# 4_Power_ON_OFF.net
KiCad netlist of a schematic drawn in Altium Designer
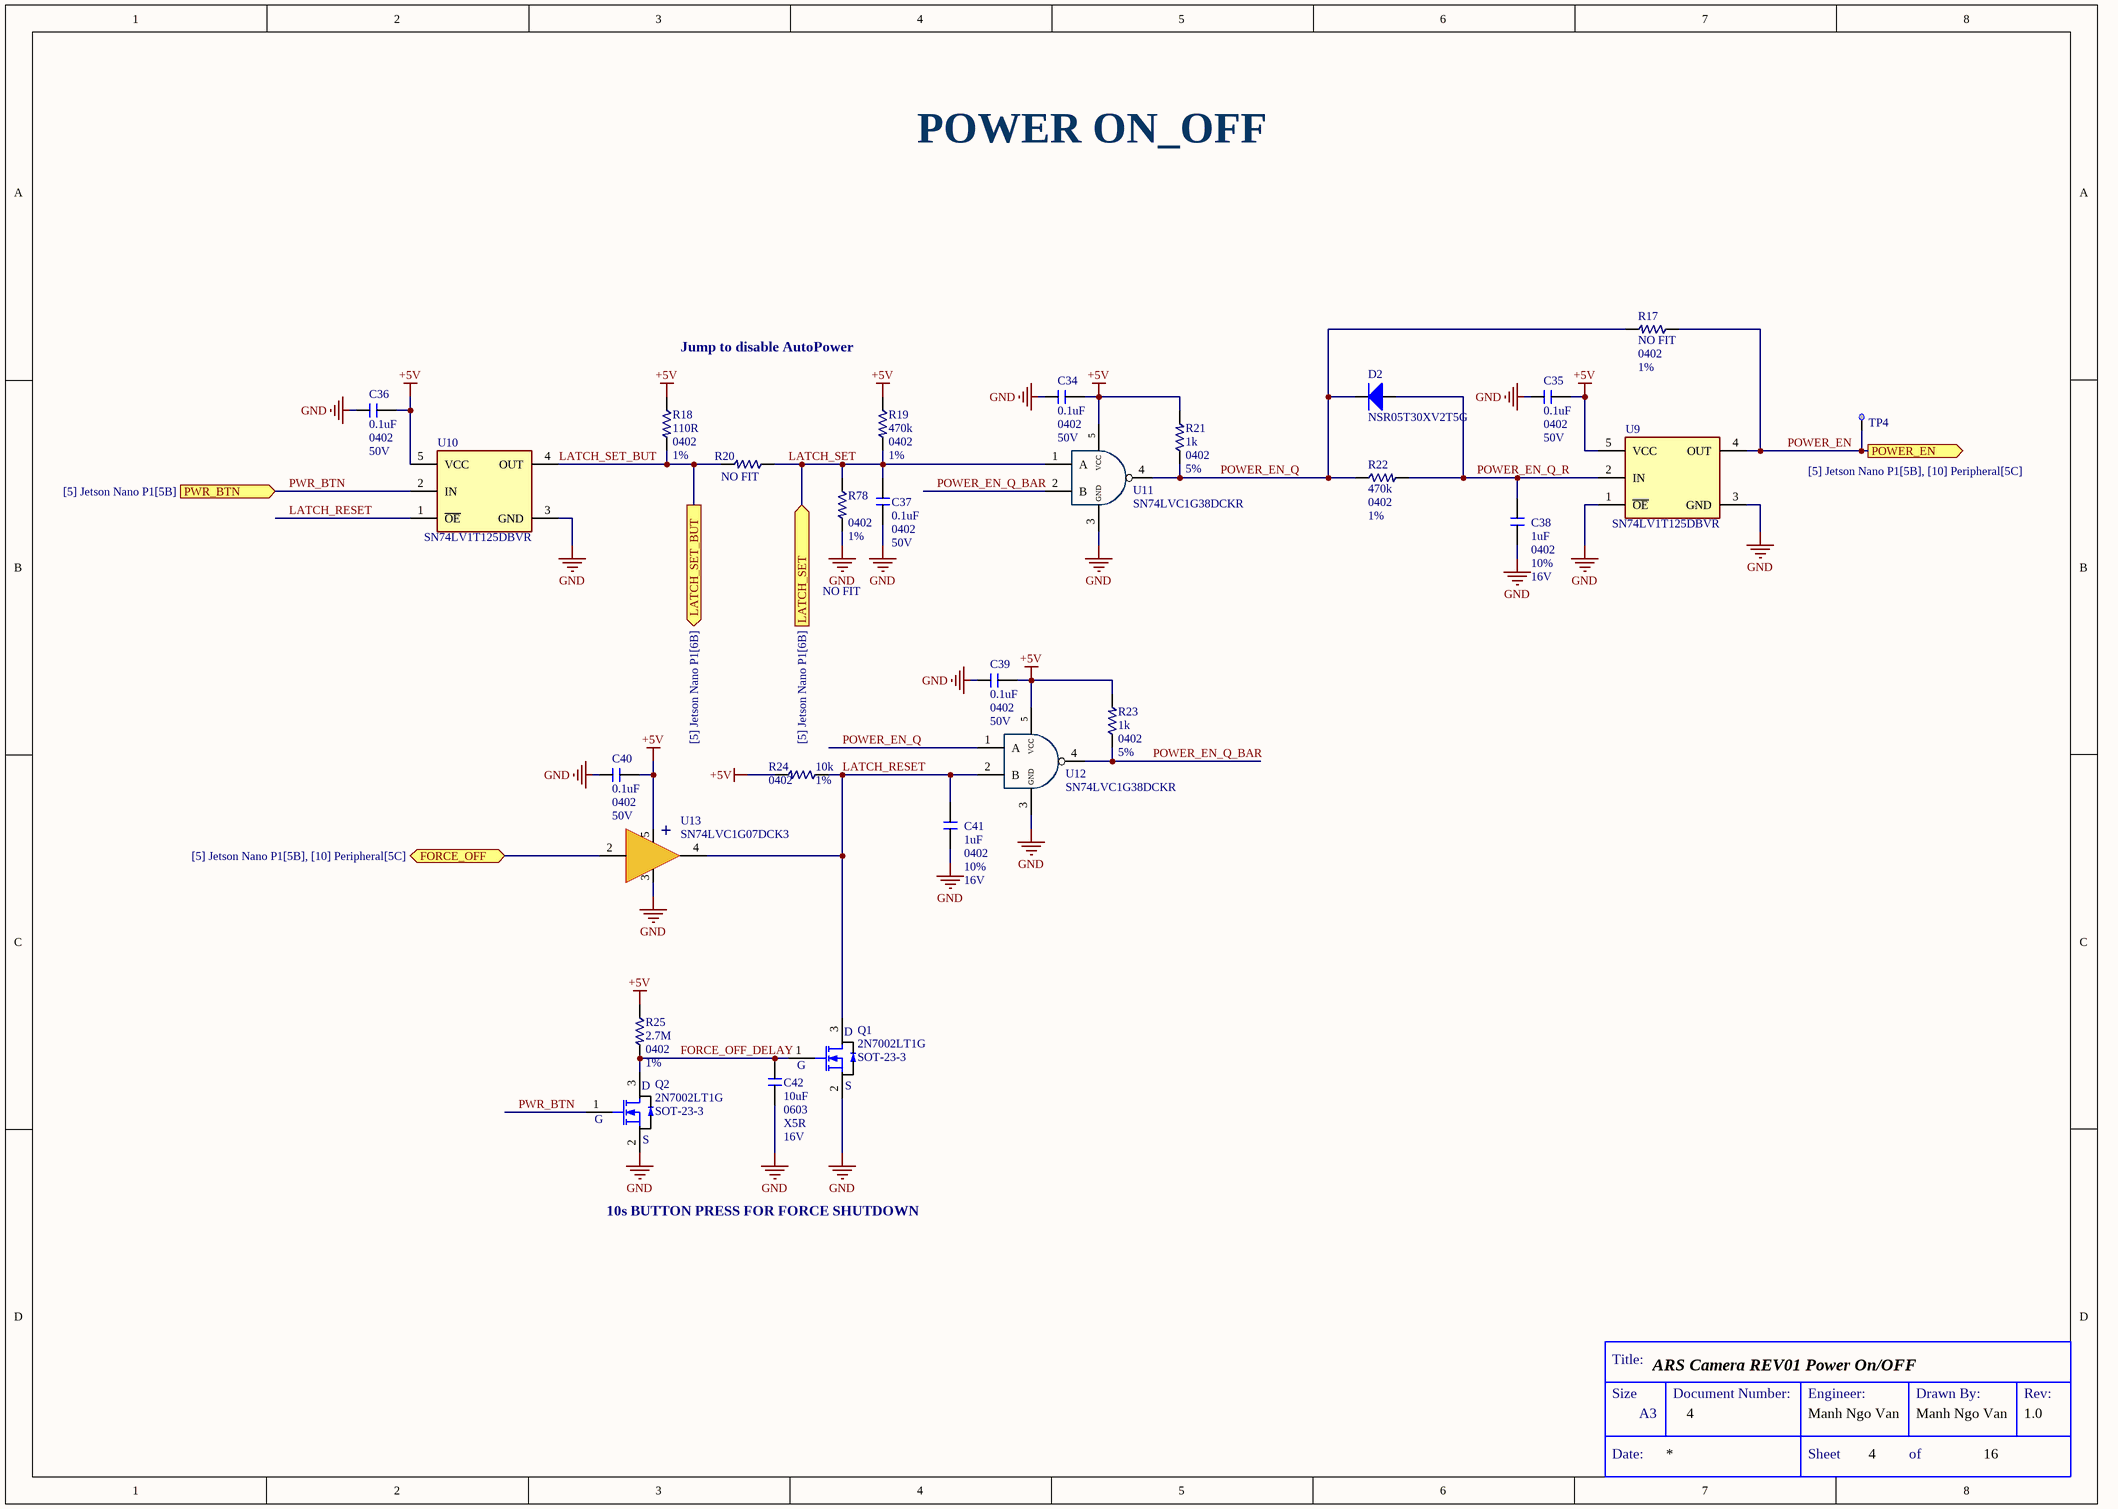
[diagram p0: [4] Power ON_OFF.SchDoc]

(export (version "E")
  (design (tool "Eeschema 10.0.6"))
  (components
    (comp (ref "C34")
      (value "0.1uF")
      (footprint "C0402M")
      (description "CAP CER 0.1UF 50V X7R 0402")
      (fields
        (field (name "MANUFACTURER") "Murata")
        (field (name "MANUFACTURER PART NUMBER") "GRM155R71H104KE14D")
        (field (name "CASE/PACKAGE") "0402")
        (field (name "VOLTAGE") "50V")
      )
      (libsource (lib "CommonLib") (part "CAP_CER"))
    )
    (comp (ref "C35")
      (value "0.1uF")
      (footprint "C0402M")
      (description "CAP CER 0.1UF 50V X7R 0402")
      (fields
        (field (name "MANUFACTURER") "Murata")
        (field (name "MANUFACTURER PART NUMBER") "GRM155R71H104KE14D")
        (field (name "CASE/PACKAGE") "0402")
        (field (name "VOLTAGE") "50V")
      )
      (libsource (lib "CommonLib") (part "CAP_CER"))
    )
    (comp (ref "C36")
      (value "0.1uF")
      (footprint "C0402M")
      (description "CAP CER 0.1UF 50V X7R 0402")
      (fields
        (field (name "MANUFACTURER") "Murata")
        (field (name "MANUFACTURER PART NUMBER") "GRM155R71H104KE14D")
        (field (name "CASE/PACKAGE") "0402")
        (field (name "VOLTAGE") "50V")
      )
      (libsource (lib "CommonLib") (part "CAP_CER"))
    )
    (comp (ref "C37")
      (value "0.1uF")
      (footprint "C0402M")
      (description "CAP CER 0.1UF 50V X7R 0402")
      (fields
        (field (name "MANUFACTURER") "Murata")
        (field (name "MANUFACTURER PART NUMBER") "GRM155R71H104KE14D")
        (field (name "CASE/PACKAGE") "0402")
        (field (name "VOLTAGE") "50V")
      )
      (libsource (lib "CommonLib") (part "CAP_CER"))
    )
    (comp (ref "C38")
      (value "1uF")
      (footprint "C0402M")
      (fields
        (field (name "CASE CODE (IMPERIAL)") "0402")
        (field (name "TOLERANCE") "10%")
        (field (name "VOLTAGE") "16V")
      )
      (libsource (lib "") (part "CAP_CER_1"))
    )
    (comp (ref "C39")
      (value "0.1uF")
      (footprint "C0402M")
      (description "CAP CER 0.1UF 50V X7R 0402")
      (fields
        (field (name "MANUFACTURER") "Murata")
        (field (name "MANUFACTURER PART NUMBER") "GRM155R71H104KE14D")
        (field (name "CASE/PACKAGE") "0402")
        (field (name "VOLTAGE") "50V")
      )
      (libsource (lib "CommonLib") (part "CAP_CER"))
    )
    (comp (ref "C40")
      (value "0.1uF")
      (footprint "C0402M")
      (description "CAP CER 0.1UF 50V X7R 0402")
      (fields
        (field (name "MANUFACTURER") "Murata")
        (field (name "MANUFACTURER PART NUMBER") "GRM155R71H104KE14D")
        (field (name "CASE/PACKAGE") "0402")
        (field (name "VOLTAGE") "50V")
      )
      (libsource (lib "CommonLib") (part "CAP_CER"))
    )
    (comp (ref "C41")
      (value "1uF")
      (footprint "C0402M")
      (fields
        (field (name "CASE CODE (IMPERIAL)") "0402")
        (field (name "TOLERANCE") "10%")
        (field (name "VOLTAGE") "16V")
      )
      (libsource (lib "") (part "CAP_CER_1"))
    )
    (comp (ref "C42")
      (value "10uF")
      (footprint "C0603M")
      (description "CAP CER 10UF 16V X5R 0603")
      (fields
        (field (name "MANUFACTURER") "Taiyo Yuden")
        (field (name "MANUFACTURER PART NUMBER") "EMK107BBJ106MA-T")
        (field (name "CASE/PACKAGE") "0603")
        (field (name "DIELECTRIC") "X5R")
        (field (name "VOLTAGE RATING (DC)") "16V")
      )
      (libsource (lib "CommonLib") (part "CAP_CER"))
    )
    (comp (ref "D2")
      (value "NSR05T30XV2T5G")
      (footprint "SODFL160X70-2N")
      (description "DIODE SCHOTTKY 30V 500MA SOD523")
      (fields (field (name "MANUFACTURER") "ON Semiconductor"))
      (libsource (lib "Altium_Library") (part "Diode"))
    )
    (comp (ref "Q1")
      (value "2N7002LT1G")
      (footprint "SOT95P245X110-3N")
      (description "MOSFET N-CH 60V 0.115A SOT-23")
      (fields (field (name "MANUFACTURER") "ON Semiconductor") (field (name "CASE/PACKAGE") "SOT-23-3"))
      (libsource (lib "CommonLib") (part "NMOS"))
    )
    (comp (ref "Q2")
      (value "2N7002LT1G")
      (footprint "SOT95P245X110-3N")
      (description "MOSFET N-CH 60V 0.115A SOT-23")
      (fields (field (name "MANUFACTURER") "ON Semiconductor") (field (name "CASE/PACKAGE") "SOT-23-3"))
      (libsource (lib "CommonLib") (part "NMOS"))
    )
    (comp (ref "R17")
      (value "NO FIT")
      (footprint "R0402M_NO_3D")
      (description "RES SMD 0 OHM JUMPER 1/16W 0402")
      (fields
        (field (name "MANUFACTURER") "Yageo")
        (field (name "MANUFACTURER PART NUMBER") "RC0402FR-070RL")
        (field (name "CASE/PACKAGE") "0402")
        (field (name "TOLERANCE") "1%")
      )
      (libsource (lib "CommonLib") (part "RES_SMD"))
    )
    (comp (ref "R18")
      (value "110R")
      (footprint "R0402M")
      (description "RES SMD 110 OHM 1% 1/16W 0402")
      (fields (field (name "CASE CODE (IMPERIAL)") "0402") (field (name "TOLERANCE") "1%"))
      (libsource (lib "CommonLib") (part "RES_SMD"))
    )
    (comp (ref "R19")
      (value "470k")
      (footprint "R0402M")
      (description "RES SMD 470K OHM 1% 1/16W 0402")
      (fields (field (name "CASE/PACKAGE") "0402") (field (name "TOLERANCE") "1%"))
      (libsource (lib "CommonLib") (part "RES_SMD"))
    )
    (comp (ref "R20")
      (value "NO FIT")
      (footprint "R0402M_NO_3D")
      (description "RES SMD 0 OHM JUMPER 1/16W 0402")
      (fields
        (field (name "MANUFACTURER") "Yageo")
        (field (name "MANUFACTURER PART NUMBER") "RC0402FR-070RL")
      )
      (libsource (lib "CommonLib") (part "RES_SMD"))
    )
    (comp (ref "R21")
      (value "1k")
      (footprint "R0402M")
      (description "RES SMD 1K OHM 5% 1/16W 0402")
      (fields
        (field (name "MANUFACTURER") "Yageo")
        (field (name "MANUFACTURER PART NUMBER") "RC0402JR-071KL")
        (field (name "CASE CODE (IMPERIAL)") "0402")
        (field (name "TOLERANCE") "5%")
      )
      (libsource (lib "CommonLib") (part "RES_SMD"))
    )
    (comp (ref "R22")
      (value "470k")
      (footprint "R0402M")
      (description "RES SMD 470K OHM 1% 1/16W 0402")
      (fields (field (name "CASE/PACKAGE") "0402") (field (name "TOLERANCE") "1%"))
      (libsource (lib "CommonLib") (part "RES_SMD"))
    )
    (comp (ref "R23")
      (value "1k")
      (footprint "R0402M")
      (description "RES SMD 1K OHM 5% 1/16W 0402")
      (fields
        (field (name "MANUFACTURER") "Yageo")
        (field (name "MANUFACTURER PART NUMBER") "RC0402JR-071KL")
        (field (name "CASE CODE (IMPERIAL)") "0402")
        (field (name "TOLERANCE") "5%")
      )
      (libsource (lib "CommonLib") (part "RES_SMD"))
    )
    (comp (ref "R24")
      (value "10k")
      (footprint "R0402M")
      (description "RES SMD 10K OHM 1% 1/16W 0402")
      (fields
        (field (name "MANUFACTURER") "Yageo")
        (field (name "MANUFACTURER PART NUMBER") "RC0402FR-0710KL")
        (field (name "CASE CODE (IMPERIAL)") "0402")
        (field (name "TOLERANCE") "1%")
      )
      (libsource (lib "CommonLib") (part "RES_SMD"))
    )
    (comp (ref "R25")
      (value "2.7M")
      (footprint "R0402M")
      (description "Res Thick Film 0402 2.7M Ohm 1% 1/16W 100ppm/C Molded SMD SMD Paper T/R")
      (fields
        (field (name "CASE CODE (IMPERIAL)") "0402")
        (field (name "TOLERANCE") "1%")
        (field (name "RESISTANCE TOLERANCE") "1%")
      )
      (libsource (lib "CommonLib") (part "RES_SMD"))
    )
    (comp (ref "R78")
      (value "NO FIT")
      (footprint "R0402M_NO_3D")
      (description "RES SMD 470K OHM 1% 1/16W 0402")
      (fields (field (name "CASE/PACKAGE") "0402") (field (name "TOLERANCE") "1%"))
      (libsource (lib "CommonLib") (part "RES_SMD"))
    )
    (comp (ref "TP4")
      (value "TP")
      (footprint "Test point")
      (description "TESTPOINT")
      (libsource (lib "CommonLib") (part "TestPoint"))
    )
    (comp (ref "U9")
      (value "SN74LV1T125DBVR")
      (footprint "SN74LV1T125DBVR")
      (description "IC BUF NON-INVERT 5.5V SOT23-5")
      (libsource (lib "NIVIA") (part "SN74LV1T125DBVR"))
    )
    (comp (ref "U10")
      (value "SN74LV1T125DBVR")
      (footprint "SN74LV1T125DBVR")
      (description "IC BUF NON-INVERT 5.5V SOT23-5")
      (libsource (lib "NIVIA") (part "SN74LV1T125DBVR"))
    )
    (comp (ref "U11")
      (value "SN74LVC1G38DCKR")
      (footprint "SOT65P210X110-5N")
      (description "IC GATE NAND 1CH 2-INP SC70-5")
      (libsource (lib "Nauvus") (part "SN74LVC1G38DCKR"))
    )
    (comp (ref "U12")
      (value "SN74LVC1G38DCKR")
      (footprint "SOT65P210X110-5N")
      (description "IC GATE NAND 1CH 2-INP SC70-5")
      (libsource (lib "Nauvus") (part "SN74LVC1G38DCKR"))
    )
    (comp (ref "U13")
      (value "SN74LVC1G07DCK3")
      (footprint "SOT65P210X110-5N")
      (description "Buffers & Line Drivers Single w/ OD")
      (fields (field (name "MANUFACTURER") "Texas Instruments"))
      (libsource (lib "Nauvus") (part "SN74LVC1G07DCKRE4"))
    )
  )
  (nets
    (net (code "1") (name "+5V") (class "Default")
      (node (ref "C34") (pin "1") (pinfunction "1_1") (pintype "passive"))
      (node (ref "C35") (pin "1") (pinfunction "1_1") (pintype "passive"))
      (node (ref "C36") (pin "1") (pinfunction "1_1") (pintype "passive"))
      (node (ref "C39") (pin "1") (pinfunction "1_1") (pintype "passive"))
      (node (ref "C40") (pin "1") (pinfunction "1_1") (pintype "passive"))
      (node (ref "R18") (pin "2") (pinfunction "2_2") (pintype "passive"))
      (node (ref "R19") (pin "2") (pinfunction "2_2") (pintype "passive"))
      (node (ref "R21") (pin "1") (pinfunction "1_1") (pintype "passive"))
      (node (ref "R23") (pin "1") (pinfunction "1_1") (pintype "passive"))
      (node (ref "R24") (pin "1") (pinfunction "1_1") (pintype "passive"))
      (node (ref "R25") (pin "2") (pinfunction "2_2") (pintype "passive"))
      (node (ref "U10") (pin "5") (pinfunction "VCC_5") (pintype "power_in"))
      (node (ref "U11") (pin "5") (pinfunction "VCC_5") (pintype "passive"))
      (node (ref "U12") (pin "5") (pinfunction "VCC_5") (pintype "passive"))
      (node (ref "U13") (pin "5") (pinfunction "VCC_5") (pintype "passive"))
      (node (ref "U9") (pin "5") (pinfunction "VCC_5") (pintype "power_in"))
    )
    (net (code "2") (name "/FORCE_OFF") (class "Default")
      (node (ref "U13") (pin "2") (pinfunction "A_2") (pintype "passive"))
    )
    (net (code "3") (name "/FORCE_OFF_DELAY") (class "Default")
      (node (ref "C42") (pin "2") (pinfunction "2_2") (pintype "passive"))
      (node (ref "Q1") (pin "1") (pinfunction "G_1") (pintype "passive"))
      (node (ref "Q2") (pin "3") (pinfunction "D_3") (pintype "passive"))
      (node (ref "R25") (pin "1") (pinfunction "1_1") (pintype "passive"))
    )
    (net (code "4") (name "/LATCH_RESET") (class "Default")
      (node (ref "C41") (pin "1") (pinfunction "1_1") (pintype "passive"))
      (node (ref "Q1") (pin "3") (pinfunction "D_3") (pintype "passive"))
      (node (ref "R24") (pin "2") (pinfunction "2_2") (pintype "passive"))
      (node (ref "U10") (pin "1") (pinfunction "~{OE}_1") (pintype "passive"))
      (node (ref "U12") (pin "2") (pinfunction "B_2") (pintype "passive"))
      (node (ref "U13") (pin "4") (pinfunction "Y_4") (pintype "passive"))
    )
    (net (code "5") (name "/LATCH_SET") (class "Default")
      (node (ref "C37") (pin "1") (pinfunction "1_1") (pintype "passive"))
      (node (ref "R19") (pin "1") (pinfunction "1_1") (pintype "passive"))
      (node (ref "R20") (pin "2") (pinfunction "2_2") (pintype "passive"))
      (node (ref "R78") (pin "2") (pinfunction "2_2") (pintype "passive"))
      (node (ref "U11") (pin "1") (pinfunction "A_1") (pintype "passive"))
    )
    (net (code "6") (name "/LATCH_SET_BUT") (class "Default")
      (node (ref "R18") (pin "1") (pinfunction "1_1") (pintype "passive"))
      (node (ref "R20") (pin "1") (pinfunction "1_1") (pintype "passive"))
      (node (ref "U10") (pin "4") (pinfunction "OUT_4") (pintype "passive"))
    )
    (net (code "7") (name "/POWER_EN") (class "Default")
      (node (ref "R17") (pin "2") (pinfunction "2_2") (pintype "passive"))
      (node (ref "TP4") (pin "1") (pinfunction "TP_1") (pintype "passive"))
      (node (ref "U9") (pin "4") (pinfunction "OUT_4") (pintype "passive"))
    )
    (net (code "8") (name "/POWER_EN_Q") (class "Default")
      (node (ref "D2") (pin "1") (pinfunction "C_1") (pintype "passive"))
      (node (ref "R17") (pin "1") (pinfunction "1_1") (pintype "passive"))
      (node (ref "R21") (pin "2") (pinfunction "2_2") (pintype "passive"))
      (node (ref "R22") (pin "2") (pinfunction "2_2") (pintype "passive"))
      (node (ref "U11") (pin "4") (pinfunction "4_4") (pintype "passive"))
      (node (ref "U12") (pin "1") (pinfunction "A_1") (pintype "passive"))
    )
    (net (code "9") (name "/POWER_EN_Q_BAR") (class "Default")
      (node (ref "R23") (pin "2") (pinfunction "2_2") (pintype "passive"))
      (node (ref "U11") (pin "2") (pinfunction "B_2") (pintype "passive"))
      (node (ref "U12") (pin "4") (pinfunction "4_4") (pintype "passive"))
    )
    (net (code "10") (name "/POWER_EN_Q_R") (class "Default")
      (node (ref "C38") (pin "1") (pinfunction "1_1") (pintype "passive"))
      (node (ref "D2") (pin "2") (pinfunction "A_2") (pintype "passive"))
      (node (ref "R22") (pin "1") (pinfunction "1_1") (pintype "passive"))
      (node (ref "U9") (pin "2") (pinfunction "IN_2") (pintype "passive"))
    )
    (net (code "11") (name "/PWR_BTN") (class "Default")
      (node (ref "Q2") (pin "1") (pinfunction "G_1") (pintype "passive"))
      (node (ref "U10") (pin "2") (pinfunction "IN_2") (pintype "passive"))
    )
    (net (code "12") (name "GND") (class "Default")
      (node (ref "C34") (pin "2") (pinfunction "2_2") (pintype "passive"))
      (node (ref "C35") (pin "2") (pinfunction "2_2") (pintype "passive"))
      (node (ref "C36") (pin "2") (pinfunction "2_2") (pintype "passive"))
      (node (ref "C37") (pin "2") (pinfunction "2_2") (pintype "passive"))
      (node (ref "C38") (pin "2") (pinfunction "2_2") (pintype "passive"))
      (node (ref "C39") (pin "2") (pinfunction "2_2") (pintype "passive"))
      (node (ref "C40") (pin "2") (pinfunction "2_2") (pintype "passive"))
      (node (ref "C41") (pin "2") (pinfunction "2_2") (pintype "passive"))
      (node (ref "C42") (pin "1") (pinfunction "1_1") (pintype "passive"))
      (node (ref "Q1") (pin "2") (pinfunction "S_2") (pintype "passive"))
      (node (ref "Q2") (pin "2") (pinfunction "S_2") (pintype "passive"))
      (node (ref "R78") (pin "1") (pinfunction "1_1") (pintype "passive"))
      (node (ref "U10") (pin "3") (pinfunction "GND_3") (pintype "power_in"))
      (node (ref "U11") (pin "3") (pinfunction "GND_3") (pintype "passive"))
      (node (ref "U12") (pin "3") (pinfunction "GND_3") (pintype "passive"))
      (node (ref "U13") (pin "3") (pinfunction "GND_3") (pintype "passive"))
      (node (ref "U9") (pin "1") (pinfunction "~{OE}_1") (pintype "passive"))
      (node (ref "U9") (pin "3") (pinfunction "GND_3") (pintype "power_in"))
    )
  )
)
